# Ham-Dip-V2-003.net
KiCad netlist of a schematic drawn in EAGLE
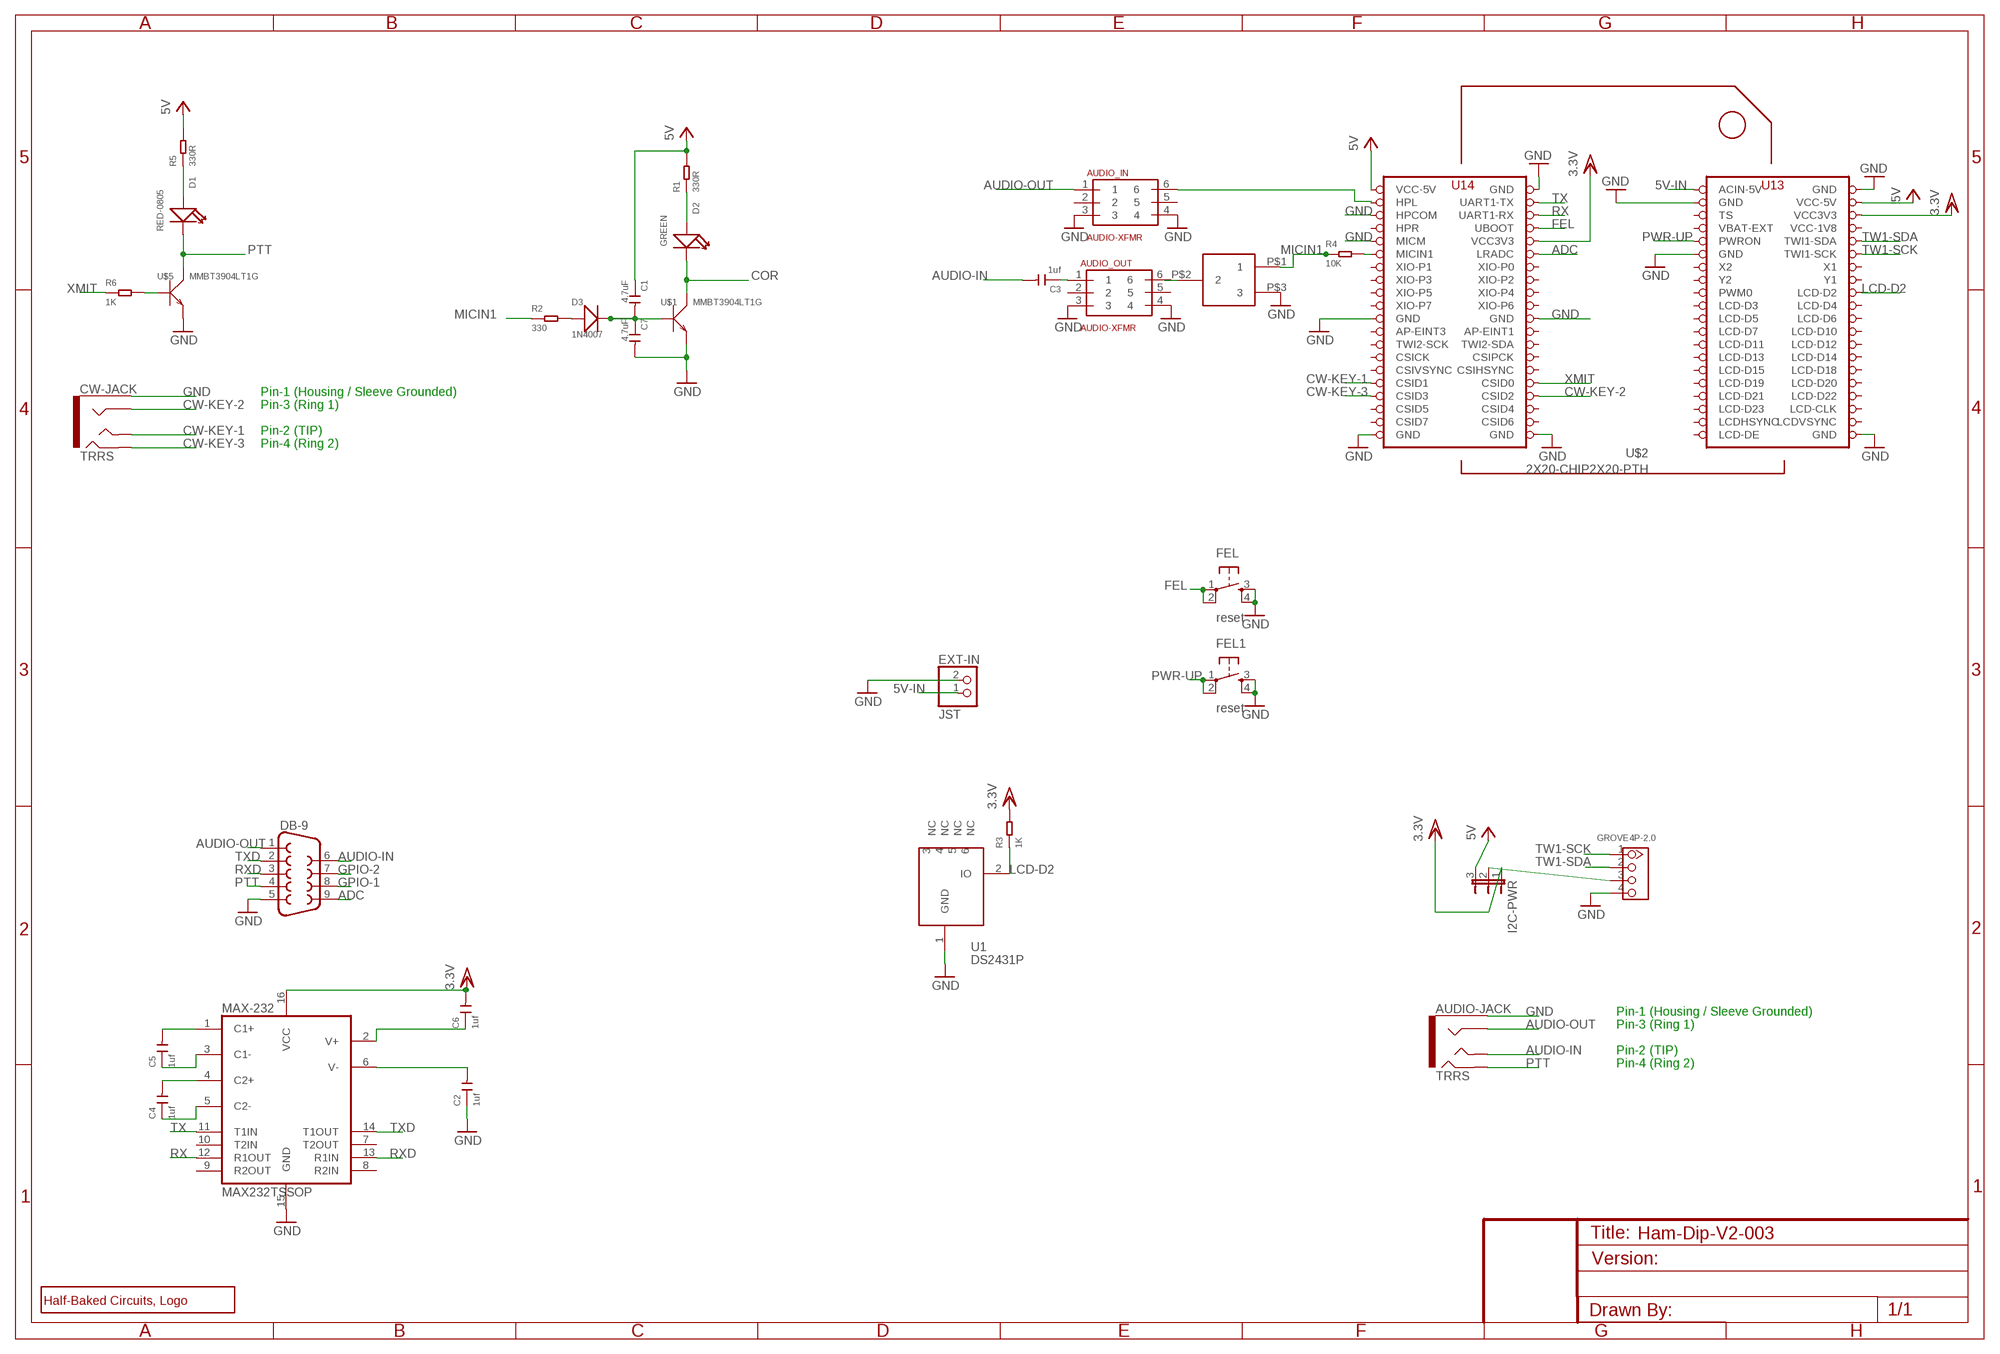
[diagram p0: schematic, sheet 1]

(export (version "E")
  (design (tool "Eeschema 10.0.6"))
  (components
    (comp (ref "AUDIO-JACK")
      (value "TRRS")
      (footprint "eagle-import:AUDIO-JACK-TRRS-SMD")
      (libsource (lib "eagle-import") (part "AUDIO-JACK3"))
    )
    (comp (ref "AUDIO_IN")
      (value "AUDIO-XFMR")
      (footprint "eagle-import:SM-LP-5001")
      (libsource (lib "eagle-import") (part "SM-LP-5001"))
    )
    (comp (ref "AUDIO_OUT")
      (value "AUDIO-XFMR")
      (footprint "eagle-import:SM-LP-5001")
      (libsource (lib "eagle-import") (part "SM-LP-5001"))
    )
    (comp (ref "C1")
      (value "4.7uF")
      (footprint "eagle-import:C0805")
      (fields (field (name "MPN") "CC0805KKX7R8BB105"))
      (libsource (lib "eagle-import") (part "CERAMIC-1UF-25V-10%-X7R(0805)"))
    )
    (comp (ref "C2")
      (value "1uf")
      (footprint "eagle-import:C0805")
      (fields (field (name "MPN") "CC0805KKX7R8BB105"))
      (libsource (lib "eagle-import") (part "CERAMIC-1UF-25V-10%-X7R(0805)"))
    )
    (comp (ref "C3")
      (value "1uf")
      (footprint "eagle-import:C0805")
      (fields (field (name "MPN") "CC0805KKX7R8BB105"))
      (libsource (lib "eagle-import") (part "CERAMIC-1UF-25V-10%-X7R(0805)"))
    )
    (comp (ref "C4")
      (value "1uf")
      (footprint "eagle-import:C0805")
      (fields (field (name "MPN") "CC0805KKX7R8BB105"))
      (libsource (lib "eagle-import") (part "CERAMIC-1UF-25V-10%-X7R(0805)"))
    )
    (comp (ref "C5")
      (value "1uf")
      (footprint "eagle-import:C0805")
      (fields (field (name "MPN") "CC0805KKX7R8BB105"))
      (libsource (lib "eagle-import") (part "CERAMIC-1UF-25V-10%-X7R(0805)"))
    )
    (comp (ref "C6")
      (value "1uf")
      (footprint "eagle-import:C0805")
      (fields (field (name "MPN") "CC0805KKX7R8BB105"))
      (libsource (lib "eagle-import") (part "CERAMIC-1UF-25V-10%-X7R(0805)"))
    )
    (comp (ref "C7")
      (value "4.7uF")
      (footprint "eagle-import:C0805")
      (fields (field (name "MPN") "CC0805KKX7R8BB105"))
      (libsource (lib "eagle-import") (part "CERAMIC-1UF-25V-10%-X7R(0805)"))
    )
    (comp (ref "CW-JACK")
      (value "TRRS")
      (footprint "eagle-import:AUDIO-JACK-TRRS-SMD")
      (libsource (lib "eagle-import") (part "AUDIO-JACK3"))
    )
    (comp (ref "D1")
      (value "RED-0805")
      (footprint "eagle-import:LED-0805")
      (fields (field (name "MPN") "17-215SURC/S530-A2/TR8"))
      (libsource (lib "eagle-import") (part "SMD-LED-CLEAR-RED(0805)"))
    )
    (comp (ref "D2")
      (value "GREEN")
      (footprint "eagle-import:LED-0805")
      (fields (field (name "MPN") "17-215SURC/S530-A2/TR8"))
      (libsource (lib "eagle-import") (part "SMD-LED-CLEAR-RED(0805)"))
    )
    (comp (ref "D3")
      (value "1N4007")
      (footprint "eagle-import:DO-214AC")
      (libsource (lib "eagle-import") (part "DIODE-GEN-PURPOSE-1KV-1A(DO-214AC)"))
    )
    (comp (ref "DB-9")
      (value "DB9FEMALE")
      (footprint "eagle-import:DB9")
      (libsource (lib "eagle-import") (part "DB9FEMALE"))
    )
    (comp (ref "EXT-IN")
      (value "JST")
      (footprint "eagle-import:JST-PH-2-THM")
      (libsource (lib "eagle-import") (part "JST_2PIN-THM"))
    )
    (comp (ref "FEL")
      (value "reset")
      (footprint "eagle-import:TACTILE_SWITCH_SMD")
      (libsource (lib "eagle-import") (part "TAC_SWITCHSMD"))
    )
    (comp (ref "FEL1")
      (value "reset")
      (footprint "eagle-import:TACTILE_SWITCH_SMD")
      (libsource (lib "eagle-import") (part "TAC_SWITCHSMD"))
    )
    (comp (ref "GROVE")
      (value "4P-2.0")
      (footprint "eagle-import:HW4-2.0")
      (libsource (lib "eagle-import") (part "GROVE-CONNECTOR-DIP(4P-2.0)"))
    )
    (comp (ref "I2C-PWR")
      (value "JP2E")
      (footprint "eagle-import:JP2")
      (libsource (lib "eagle-import") (part "JP2E"))
    )
    (comp (ref "MAX-232")
      (value "MAX232TSSOP")
      (footprint "eagle-import:TSSOP16")
      (libsource (lib "eagle-import") (part "MAX232TSSOP"))
    )
    (comp (ref "R1")
      (value "330R")
      (footprint "eagle-import:R0805")
      (fields (field (name "MPN") "RC0805JR-07220RL"))
      (libsource (lib "eagle-import") (part "SMD-RES-220R-5%-1/8W(0805)"))
    )
    (comp (ref "R2")
      (value "330")
      (footprint "eagle-import:R0805")
      (fields (field (name "MPN") "RC0805JR-07220RL"))
      (libsource (lib "eagle-import") (part "SMD-RES-220R-5%-1/8W(0805)"))
    )
    (comp (ref "R3")
      (value "1K")
      (footprint "eagle-import:R0805")
      (fields (field (name "MPN") "RC0805JR-07220RL"))
      (libsource (lib "eagle-import") (part "SMD-RES-220R-5%-1/8W(0805)"))
    )
    (comp (ref "R4")
      (value "10K")
      (footprint "eagle-import:R0805")
      (fields (field (name "MPN") "RC0805FR-0710KL"))
      (libsource (lib "eagle-import") (part "SMD-RES-10K-1%-1/8W(0805)"))
    )
    (comp (ref "R5")
      (value "330R")
      (footprint "eagle-import:R0805")
      (fields (field (name "MPN") "RC0805JR-07220RL"))
      (libsource (lib "eagle-import") (part "SMD-RES-220R-5%-1/8W(0805)"))
    )
    (comp (ref "R6")
      (value "1K")
      (footprint "eagle-import:R0805")
      (fields (field (name "MPN") "RC0805JR-07220RL"))
      (libsource (lib "eagle-import") (part "SMD-RES-220R-5%-1/8W(0805)"))
    )
    (comp (ref "U$1")
      (value "MMBT3904LT1G")
      (footprint "eagle-import:SOT-23")
      (libsource (lib "eagle-import") (part "SMD-TRANSISTORS-NPN-40V-200MA-MMBT3904LT1G(SOT-23)"))
    )
    (comp (ref "U$2")
      (value "2X20-CHIP2X20-PTH")
      (footprint "eagle-import:2X20CHIP-TH")
      (fields (field (name "VENDOR_PART_NUMBER") "AWHW40-G-SMD-R (single)"))
      (libsource (lib "eagle-import") (part "2X20-CHIP2X20-PTH-CHIP_A"))
    )
    (comp (ref "U$3")
      (value "TC33X")
      (footprint "eagle-import:TC33X")
      (libsource (lib "eagle-import") (part "TC33X"))
    )
    (comp (ref "U$4")
      (value "HAM-DIP")
      (footprint "eagle-import:HAM-DIP")
      (libsource (lib "eagle-import") (part "HAM-DIP"))
    )
    (comp (ref "U$5")
      (value "MMBT3904LT1G")
      (footprint "eagle-import:SOT-23")
      (libsource (lib "eagle-import") (part "SMD-TRANSISTORS-NPN-40V-200MA-MMBT3904LT1G(SOT-23)"))
    )
    (comp (ref "U1")
      (value "DS2431P")
      (footprint "eagle-import:TSOC6")
      (fields (field (name "MFG") "DIGIKEY") (field (name "VENDOR_PART_NUMBER") "DS2431P+T&R"))
      (libsource (lib "eagle-import") (part "DS2431P"))
    )
  )
  (nets
    (net (code "1") (name "/5V-IN") (class "Default")
      (node (ref "EXT-IN") (pin "1") (pinfunction "2_1") (pintype "passive"))
      (node (ref "U$2") (pin "CHG-IN") (pinfunction "ACIN-5V_CHG-IN") (pintype "passive"))
    )
    (net (code "2") (name "/ADC") (class "Default")
      (node (ref "DB-9") (pin "9") (pinfunction "9_9") (pintype "passive"))
      (node (ref "U$2") (pin "LRADC") (pinfunction "LRADC_LRADC") (pintype "passive"))
    )
    (net (code "3") (name "/AUDIO-IN") (class "Default")
      (node (ref "AUDIO-JACK") (pin "TIP") (pinfunction "TIP_TIP") (pintype "bidirectional"))
      (node (ref "C3") (pin "2") (pinfunction "2_2") (pintype "passive"))
      (node (ref "DB-9") (pin "6") (pinfunction "6_6") (pintype "passive"))
    )
    (net (code "4") (name "/AUDIO-OUT") (class "Default")
      (node (ref "AUDIO-JACK") (pin "RING1") (pinfunction "RING1_RING1") (pintype "bidirectional"))
      (node (ref "AUDIO_IN") (pin "1") (pinfunction "1_1") (pintype "bidirectional"))
      (node (ref "DB-9") (pin "1") (pinfunction "1_1") (pintype "passive"))
    )
    (net (code "5") (name "/COR") (class "Default")
      (node (ref "D2") (pin "-") (pinfunction "-_-") (pintype "passive"))
      (node (ref "U$1") (pin "3") (pinfunction "C_3") (pintype "passive"))
    )
    (net (code "6") (name "/CW-KEY-1") (class "Default")
      (node (ref "CW-JACK") (pin "TIP") (pinfunction "TIP_TIP") (pintype "bidirectional"))
      (node (ref "U$2") (pin "CSID1") (pinfunction "CSID1_CSID1") (pintype "passive"))
    )
    (net (code "7") (name "/CW-KEY-2") (class "Default")
      (node (ref "CW-JACK") (pin "RING1") (pinfunction "RING1_RING1") (pintype "bidirectional"))
      (node (ref "U$2") (pin "CSID2") (pinfunction "CSID2_CSID2") (pintype "passive"))
    )
    (net (code "8") (name "/CW-KEY-3") (class "Default")
      (node (ref "CW-JACK") (pin "RING2") (pinfunction "RING2_RING2") (pintype "bidirectional"))
      (node (ref "U$2") (pin "CSID3") (pinfunction "CSID3_CSID3") (pintype "passive"))
    )
    (net (code "9") (name "/FEL") (class "Default")
      (node (ref "FEL") (pin "1") (pinfunction "1_1") (pintype "passive"))
      (node (ref "FEL") (pin "2") (pinfunction "2_2") (pintype "passive"))
      (node (ref "U$2") (pin "FEL") (pinfunction "UBOOT_FEL") (pintype "passive"))
    )
    (net (code "10") (name "/GPIO-1") (class "Default")
      (node (ref "DB-9") (pin "8") (pinfunction "8_8") (pintype "passive"))
    )
    (net (code "11") (name "/GPIO-2") (class "Default")
      (node (ref "DB-9") (pin "7") (pinfunction "7_7") (pintype "passive"))
    )
    (net (code "12") (name "/LCD-D2") (class "Default")
      (node (ref "R3") (pin "1") (pinfunction "1_1") (pintype "passive"))
      (node (ref "U$2") (pin "LCD-D2") (pinfunction "LCD-D2_LCD-D2") (pintype "passive"))
      (node (ref "U1") (pin "2") (pinfunction "IO_2") (pintype "bidirectional"))
    )
    (net (code "13") (name "/MICIN1") (class "Default")
      (node (ref "R2") (pin "1") (pinfunction "1_1") (pintype "passive"))
      (node (ref "R4") (pin "2") (pinfunction "2_2") (pintype "passive"))
      (node (ref "U$2") (pin "MICIN1") (pinfunction "MICIN1_MICIN1") (pintype "passive"))
    )
    (net (code "14") (name "/PTT") (class "Default")
      (node (ref "AUDIO-JACK") (pin "RING2") (pinfunction "RING2_RING2") (pintype "bidirectional"))
      (node (ref "D1") (pin "-") (pinfunction "-_-") (pintype "passive"))
      (node (ref "DB-9") (pin "4") (pinfunction "4_4") (pintype "passive"))
      (node (ref "U$5") (pin "3") (pinfunction "C_3") (pintype "passive"))
    )
    (net (code "15") (name "/PWR-UP") (class "Default")
      (node (ref "FEL1") (pin "1") (pinfunction "1_1") (pintype "passive"))
      (node (ref "FEL1") (pin "2") (pinfunction "2_2") (pintype "passive"))
      (node (ref "U$2") (pin "PWRON") (pinfunction "PWRON_PWRON") (pintype "passive"))
    )
    (net (code "16") (name "/RX") (class "Default")
      (node (ref "MAX-232") (pin "12") (pinfunction "R1OUT_12") (pintype "output"))
      (node (ref "U$2") (pin "UART1-RX") (pinfunction "UART1-RX_UART1-RX") (pintype "passive"))
    )
    (net (code "17") (name "/RXD") (class "Default")
      (node (ref "DB-9") (pin "3") (pinfunction "3_3") (pintype "passive"))
      (node (ref "MAX-232") (pin "13") (pinfunction "R1IN_13") (pintype "input"))
    )
    (net (code "18") (name "/TW1-SCK") (class "Default")
      (node (ref "GROVE") (pin "1") (pinfunction "1_1") (pintype "bidirectional"))
      (node (ref "U$2") (pin "TWI1-SCK") (pinfunction "TWI1-SCK_TWI1-SCK") (pintype "passive"))
    )
    (net (code "19") (name "/TW1-SDA") (class "Default")
      (node (ref "GROVE") (pin "2") (pinfunction "2_2") (pintype "bidirectional"))
      (node (ref "U$2") (pin "TWI1-SDA") (pinfunction "TWI1-SDA_TWI1-SDA") (pintype "passive"))
    )
    (net (code "20") (name "/TX") (class "Default")
      (node (ref "MAX-232") (pin "11") (pinfunction "T1IN_11") (pintype "input"))
      (node (ref "U$2") (pin "UART1-TX") (pinfunction "UART1-TX_UART1-TX") (pintype "passive"))
    )
    (net (code "21") (name "/TXD") (class "Default")
      (node (ref "DB-9") (pin "2") (pinfunction "2_2") (pintype "passive"))
      (node (ref "MAX-232") (pin "14") (pinfunction "T1OUT_14") (pintype "output"))
    )
    (net (code "22") (name "/VCC-1V8") (class "Default")
      (node (ref "U$2") (pin "VCC1V8") (pinfunction "VCC-1V8_VCC1V8") (pintype "power_in"))
    )
    (net (code "23") (name "/XMIT") (class "Default")
      (node (ref "R6") (pin "1") (pinfunction "1_1") (pintype "passive"))
      (node (ref "U$2") (pin "CSID0") (pinfunction "CSID0_CSID0") (pintype "passive"))
    )
    (net (code "24") (name "3.3V") (class "Default")
      (node (ref "C6") (pin "2") (pinfunction "2_2") (pintype "passive"))
      (node (ref "I2C-PWR") (pin "1") (pinfunction "1_1") (pintype "passive"))
      (node (ref "MAX-232") (pin "16") (pinfunction "VCC_16") (pintype "bidirectional"))
      (node (ref "R3") (pin "2") (pinfunction "2_2") (pintype "passive"))
      (node (ref "U$2") (pin "VCC3V3") (pinfunction "VCC3V3_VCC3V3") (pintype "power_in"))
      (node (ref "U$2") (pin "VCC3V3@1") (pinfunction "VCC3V3_VCC3V3@1") (pintype "power_in"))
    )
    (net (code "25") (name "5V") (class "Default")
      (node (ref "C1") (pin "1") (pinfunction "1_1") (pintype "passive"))
      (node (ref "I2C-PWR") (pin "3") (pinfunction "3_3") (pintype "passive"))
      (node (ref "R1") (pin "2") (pinfunction "2_2") (pintype "passive"))
      (node (ref "R5") (pin "2") (pinfunction "2_2") (pintype "passive"))
      (node (ref "U$2") (pin "VCC5V@0") (pinfunction "VCC-5V_VCC5V@0") (pintype "power_in"))
      (node (ref "U$2") (pin "VCC5V@1") (pinfunction "VCC-5V_VCC5V@1") (pintype "power_in"))
    )
    (net (code "26") (name "GND") (class "Default")
      (node (ref "AUDIO-JACK") (pin "EARTH") (pinfunction "EARTH_EARTH") (pintype "bidirectional"))
      (node (ref "AUDIO_IN") (pin "3") (pinfunction "3_3") (pintype "bidirectional"))
      (node (ref "AUDIO_IN") (pin "4") (pinfunction "4_4") (pintype "bidirectional"))
      (node (ref "AUDIO_OUT") (pin "3") (pinfunction "3_3") (pintype "bidirectional"))
      (node (ref "AUDIO_OUT") (pin "4") (pinfunction "4_4") (pintype "bidirectional"))
      (node (ref "C2") (pin "1") (pinfunction "1_1") (pintype "passive"))
      (node (ref "C7") (pin "2") (pinfunction "2_2") (pintype "passive"))
      (node (ref "CW-JACK") (pin "EARTH") (pinfunction "EARTH_EARTH") (pintype "bidirectional"))
      (node (ref "DB-9") (pin "5") (pinfunction "5_5") (pintype "passive"))
      (node (ref "EXT-IN") (pin "2") (pinfunction "1_2") (pintype "passive"))
      (node (ref "FEL") (pin "3") (pinfunction "3_3") (pintype "passive"))
      (node (ref "FEL") (pin "4") (pinfunction "4_4") (pintype "passive"))
      (node (ref "FEL1") (pin "3") (pinfunction "3_3") (pintype "passive"))
      (node (ref "FEL1") (pin "4") (pinfunction "4_4") (pintype "passive"))
      (node (ref "GROVE") (pin "4") (pinfunction "4_4") (pintype "bidirectional"))
      (node (ref "MAX-232") (pin "15") (pinfunction "GND_15") (pintype "bidirectional"))
      (node (ref "U$1") (pin "2") (pinfunction "E_2") (pintype "passive"))
      (node (ref "U$2") (pin "GND@1") (pinfunction "GND_GND@1") (pintype "power_in"))
      (node (ref "U$2") (pin "GND@10") (pinfunction "GND_GND@10") (pintype "power_in"))
      (node (ref "U$2") (pin "GND@2") (pinfunction "GND_GND@2") (pintype "power_in"))
      (node (ref "U$2") (pin "GND@3") (pinfunction "GND_GND@3") (pintype "power_in"))
      (node (ref "U$2") (pin "GND@4") (pinfunction "GND_GND@4") (pintype "power_in"))
      (node (ref "U$2") (pin "GND@5") (pinfunction "GND_GND@5") (pintype "power_in"))
      (node (ref "U$2") (pin "GND@6") (pinfunction "GND_GND@6") (pintype "power_in"))
      (node (ref "U$2") (pin "GND@7") (pinfunction "GND_GND@7") (pintype "power_in"))
      (node (ref "U$2") (pin "GND@8") (pinfunction "GND_GND@8") (pintype "power_in"))
      (node (ref "U$2") (pin "HPCOM") (pinfunction "HPCOM_HPCOM") (pintype "passive"))
      (node (ref "U$2") (pin "MICM") (pinfunction "MICM_MICM") (pintype "passive"))
      (node (ref "U$3") (pin "P$3") (pinfunction "3_P$3") (pintype "bidirectional"))
      (node (ref "U$5") (pin "2") (pinfunction "E_2") (pintype "passive"))
      (node (ref "U1") (pin "1") (pinfunction "GND_1") (pintype "bidirectional"))
    )
    (net (code "27") (name "Net-(AUDIO_IN-Pad6)") (class "Default")
      (node (ref "AUDIO_IN") (pin "6") (pinfunction "6_6") (pintype "bidirectional"))
      (node (ref "U$2") (pin "HPL") (pinfunction "HPL_HPL") (pintype "passive"))
    )
    (net (code "28") (name "Net-(AUDIO_OUT-Pad1)") (class "Default")
      (node (ref "AUDIO_OUT") (pin "1") (pinfunction "1_1") (pintype "bidirectional"))
      (node (ref "C3") (pin "1") (pinfunction "1_1") (pintype "passive"))
    )
    (net (code "29") (name "Net-(D1-Pad+)") (class "Default")
      (node (ref "D1") (pin "+") (pinfunction "+_+") (pintype "passive"))
      (node (ref "R5") (pin "1") (pinfunction "1_1") (pintype "passive"))
    )
    (net (code "30") (name "Net-(D2-Pad+)") (class "Default")
      (node (ref "D2") (pin "+") (pinfunction "+_+") (pintype "passive"))
      (node (ref "R1") (pin "1") (pinfunction "1_1") (pintype "passive"))
    )
    (net (code "31") (name "Net-(D3-+)") (class "Default")
      (node (ref "D3") (pin "1") (pinfunction "+_1") (pintype "passive"))
      (node (ref "R2") (pin "2") (pinfunction "2_2") (pintype "passive"))
    )
    (net (code "32") (name "Net-(D3--)") (class "Default")
      (node (ref "C1") (pin "2") (pinfunction "2_2") (pintype "passive"))
      (node (ref "C7") (pin "1") (pinfunction "1_1") (pintype "passive"))
      (node (ref "D3") (pin "2") (pinfunction "-_2") (pintype "passive"))
      (node (ref "U$1") (pin "1") (pinfunction "B_1") (pintype "passive"))
    )
    (net (code "33") (name "Net-(GROVE-Pad3)") (class "Default")
      (node (ref "GROVE") (pin "3") (pinfunction "3_3") (pintype "bidirectional"))
      (node (ref "I2C-PWR") (pin "2") (pinfunction "2_2") (pintype "passive"))
    )
    (net (code "34") (name "Net-(MAX-232-C1+)") (class "Default")
      (node (ref "C5") (pin "2") (pinfunction "2_2") (pintype "passive"))
      (node (ref "MAX-232") (pin "1") (pinfunction "C1+_1") (pintype "bidirectional"))
    )
    (net (code "35") (name "Net-(MAX-232-C1-)") (class "Default")
      (node (ref "C5") (pin "1") (pinfunction "1_1") (pintype "passive"))
      (node (ref "MAX-232") (pin "3") (pinfunction "C1-_3") (pintype "bidirectional"))
    )
    (net (code "36") (name "Net-(MAX-232-C2+)") (class "Default")
      (node (ref "C4") (pin "2") (pinfunction "2_2") (pintype "passive"))
      (node (ref "MAX-232") (pin "4") (pinfunction "C2+_4") (pintype "bidirectional"))
    )
    (net (code "37") (name "Net-(MAX-232-C2-)") (class "Default")
      (node (ref "C4") (pin "1") (pinfunction "1_1") (pintype "passive"))
      (node (ref "MAX-232") (pin "5") (pinfunction "C2-_5") (pintype "bidirectional"))
    )
    (net (code "38") (name "Net-(MAX-232-V+)") (class "Default")
      (node (ref "C6") (pin "1") (pinfunction "1_1") (pintype "passive"))
      (node (ref "MAX-232") (pin "2") (pinfunction "V+_2") (pintype "bidirectional"))
    )
    (net (code "39") (name "Net-(MAX-232-V-)") (class "Default")
      (node (ref "C2") (pin "2") (pinfunction "2_2") (pintype "passive"))
      (node (ref "MAX-232") (pin "6") (pinfunction "V-_6") (pintype "bidirectional"))
    )
    (net (code "40") (name "Net-(U$3-1)") (class "Default")
      (node (ref "R4") (pin "1") (pinfunction "1_1") (pintype "passive"))
      (node (ref "U$3") (pin "P$1") (pinfunction "1_P$1") (pintype "bidirectional"))
    )
    (net (code "41") (name "Net-(U$5-B)") (class "Default")
      (node (ref "R6") (pin "2") (pinfunction "2_2") (pintype "passive"))
      (node (ref "U$5") (pin "1") (pinfunction "B_1") (pintype "passive"))
    )
    (net (code "42") (name "unconnected-(AUDIO_IN-Pad2)") (class "Default")
      (node (ref "AUDIO_IN") (pin "2") (pinfunction "2_2") (pintype "bidirectional"))
    )
    (net (code "43") (name "unconnected-(AUDIO_IN-Pad5)") (class "Default")
      (node (ref "AUDIO_IN") (pin "5") (pinfunction "5_5") (pintype "bidirectional"))
    )
    (net (code "44") (name "unconnected-(AUDIO_OUT-Pad2)") (class "Default")
      (node (ref "AUDIO_OUT") (pin "2") (pinfunction "2_2") (pintype "bidirectional"))
    )
    (net (code "45") (name "unconnected-(AUDIO_OUT-Pad5)") (class "Default")
      (node (ref "AUDIO_OUT") (pin "5") (pinfunction "5_5") (pintype "bidirectional"))
    )
    (net (code "46") (name "unconnected-(AUDIO_OUT-Pad6)") (class "Default")
      (node (ref "AUDIO_OUT") (pin "6") (pinfunction "6_6") (pintype "bidirectional"))
    )
    (net (code "47") (name "unconnected-(MAX-232-R2IN-Pad8)") (class "Default")
      (node (ref "MAX-232") (pin "8") (pinfunction "R2IN_8") (pintype "input"))
    )
    (net (code "48") (name "unconnected-(MAX-232-R2OUT-Pad9)") (class "Default")
      (node (ref "MAX-232") (pin "9") (pinfunction "R2OUT_9") (pintype "output"))
    )
    (net (code "49") (name "unconnected-(MAX-232-T2IN-Pad10)") (class "Default")
      (node (ref "MAX-232") (pin "10") (pinfunction "T2IN_10") (pintype "input"))
    )
    (net (code "50") (name "unconnected-(MAX-232-T2OUT-Pad7)") (class "Default")
      (node (ref "MAX-232") (pin "7") (pinfunction "T2OUT_7") (pintype "output"))
    )
    (net (code "51") (name "unconnected-(U$2-LCDHSYNC-PadLCD-HSYNC)") (class "Default")
      (node (ref "U$2") (pin "LCD-HSYNC") (pinfunction "LCDHSYNC_LCD-HSYNC") (pintype "passive"))
    )
    (net (code "52") (name "unconnected-(U$2-LCDVSYNC-PadLCD-VSYNC)") (class "Default")
      (node (ref "U$2") (pin "LCD-VSYNC") (pinfunction "LCDVSYNC_LCD-VSYNC") (pintype "passive"))
    )
    (net (code "53") (name "unconnected-(U$2-PadAP-EINT1)") (class "Default")
      (node (ref "U$2") (pin "AP-EINT1") (pinfunction "AP-EINT1_AP-EINT1") (pintype "passive"))
    )
    (net (code "54") (name "unconnected-(U$2-PadAP-EINT3)") (class "Default")
      (node (ref "U$2") (pin "AP-EINT3") (pinfunction "AP-EINT3_AP-EINT3") (pintype "passive"))
    )
    (net (code "55") (name "unconnected-(U$2-PadCSICK)") (class "Default")
      (node (ref "U$2") (pin "CSICK") (pinfunction "CSICK_CSICK") (pintype "passive"))
    )
    (net (code "56") (name "unconnected-(U$2-PadCSID4)") (class "Default")
      (node (ref "U$2") (pin "CSID4") (pinfunction "CSID4_CSID4") (pintype "passive"))
    )
    (net (code "57") (name "unconnected-(U$2-PadCSID5)") (class "Default")
      (node (ref "U$2") (pin "CSID5") (pinfunction "CSID5_CSID5") (pintype "passive"))
    )
    (net (code "58") (name "unconnected-(U$2-PadCSID6)") (class "Default")
      (node (ref "U$2") (pin "CSID6") (pinfunction "CSID6_CSID6") (pintype "passive"))
    )
    (net (code "59") (name "unconnected-(U$2-PadCSID7)") (class "Default")
      (node (ref "U$2") (pin "CSID7") (pinfunction "CSID7_CSID7") (pintype "passive"))
    )
    (net (code "60") (name "unconnected-(U$2-PadCSIHSYNC)") (class "Default")
      (node (ref "U$2") (pin "CSIHSYNC") (pinfunction "CSIHSYNC_CSIHSYNC") (pintype "passive"))
    )
    (net (code "61") (name "unconnected-(U$2-PadCSIPCK)") (class "Default")
      (node (ref "U$2") (pin "CSIPCK") (pinfunction "CSIPCK_CSIPCK") (pintype "passive"))
    )
    (net (code "62") (name "unconnected-(U$2-PadCSIVSYNC)") (class "Default")
      (node (ref "U$2") (pin "CSIVSYNC") (pinfunction "CSIVSYNC_CSIVSYNC") (pintype "passive"))
    )
    (net (code "63") (name "unconnected-(U$2-PadHPR)") (class "Default")
      (node (ref "U$2") (pin "HPR") (pinfunction "HPR_HPR") (pintype "passive"))
    )
    (net (code "64") (name "unconnected-(U$2-PadLCD-CLK)") (class "Default")
      (node (ref "U$2") (pin "LCD-CLK") (pinfunction "LCD-CLK_LCD-CLK") (pintype "passive"))
    )
    (net (code "65") (name "unconnected-(U$2-PadLCD-D3)") (class "Default")
      (node (ref "U$2") (pin "LCD-D3") (pinfunction "LCD-D3_LCD-D3") (pintype "passive"))
    )
    (net (code "66") (name "unconnected-(U$2-PadLCD-D4)") (class "Default")
      (node (ref "U$2") (pin "LCD-D4") (pinfunction "LCD-D4_LCD-D4") (pintype "passive"))
    )
    (net (code "67") (name "unconnected-(U$2-PadLCD-D5)") (class "Default")
      (node (ref "U$2") (pin "LCD-D5") (pinfunction "LCD-D5_LCD-D5") (pintype "passive"))
    )
    (net (code "68") (name "unconnected-(U$2-PadLCD-D6)") (class "Default")
      (node (ref "U$2") (pin "LCD-D6") (pinfunction "LCD-D6_LCD-D6") (pintype "passive"))
    )
    (net (code "69") (name "unconnected-(U$2-PadLCD-D7)") (class "Default")
      (node (ref "U$2") (pin "LCD-D7") (pinfunction "LCD-D7_LCD-D7") (pintype "passive"))
    )
    (net (code "70") (name "unconnected-(U$2-PadLCD-D10)") (class "Default")
      (node (ref "U$2") (pin "LCD-D10") (pinfunction "LCD-D10_LCD-D10") (pintype "passive"))
    )
    (net (code "71") (name "unconnected-(U$2-PadLCD-D11)") (class "Default")
      (node (ref "U$2") (pin "LCD-D11") (pinfunction "LCD-D11_LCD-D11") (pintype "passive"))
    )
    (net (code "72") (name "unconnected-(U$2-PadLCD-D12)") (class "Default")
      (node (ref "U$2") (pin "LCD-D12") (pinfunction "LCD-D12_LCD-D12") (pintype "passive"))
    )
    (net (code "73") (name "unconnected-(U$2-PadLCD-D13)") (class "Default")
      (node (ref "U$2") (pin "LCD-D13") (pinfunction "LCD-D13_LCD-D13") (pintype "passive"))
    )
    (net (code "74") (name "unconnected-(U$2-PadLCD-D14)") (class "Default")
      (node (ref "U$2") (pin "LCD-D14") (pinfunction "LCD-D14_LCD-D14") (pintype "passive"))
    )
    (net (code "75") (name "unconnected-(U$2-PadLCD-D15)") (class "Default")
      (node (ref "U$2") (pin "LCD-D15") (pinfunction "LCD-D15_LCD-D15") (pintype "passive"))
    )
    (net (code "76") (name "unconnected-(U$2-PadLCD-D18)") (class "Default")
      (node (ref "U$2") (pin "LCD-D18") (pinfunction "LCD-D18_LCD-D18") (pintype "passive"))
    )
    (net (code "77") (name "unconnected-(U$2-PadLCD-D19)") (class "Default")
      (node (ref "U$2") (pin "LCD-D19") (pinfunction "LCD-D19_LCD-D19") (pintype "passive"))
    )
    (net (code "78") (name "unconnected-(U$2-PadLCD-D20)") (class "Default")
      (node (ref "U$2") (pin "LCD-D20") (pinfunction "LCD-D20_LCD-D20") (pintype "passive"))
    )
    (net (code "79") (name "unconnected-(U$2-PadLCD-D21)") (class "Default")
      (node (ref "U$2") (pin "LCD-D21") (pinfunction "LCD-D21_LCD-D21") (pintype "passive"))
    )
    (net (code "80") (name "unconnected-(U$2-PadLCD-D22)") (class "Default")
      (node (ref "U$2") (pin "LCD-D22") (pinfunction "LCD-D22_LCD-D22") (pintype "passive"))
    )
    (net (code "81") (name "unconnected-(U$2-PadLCD-D23)") (class "Default")
      (node (ref "U$2") (pin "LCD-D23") (pinfunction "LCD-D23_LCD-D23") (pintype "passive"))
    )
    (net (code "82") (name "unconnected-(U$2-PadLCD-DE)") (class "Default")
      (node (ref "U$2") (pin "LCD-DE") (pinfunction "LCD-DE_LCD-DE") (pintype "passive"))
    )
    (net (code "83") (name "unconnected-(U$2-PadPWM0)") (class "Default")
      (node (ref "U$2") (pin "PWM0") (pinfunction "PWM0_PWM0") (pintype "passive"))
    )
    (net (code "84") (name "unconnected-(U$2-PadTS)") (class "Default")
      (node (ref "U$2") (pin "TS") (pinfunction "TS_TS") (pintype "passive"))
    )
    (net (code "85") (name "unconnected-(U$2-PadTWI2-SCK)") (class "Default")
      (node (ref "U$2") (pin "TWI2-SCK") (pinfunction "TWI2-SCK_TWI2-SCK") (pintype "passive"))
    )
    (net (code "86") (name "unconnected-(U$2-PadTWI2-SDA)") (class "Default")
      (node (ref "U$2") (pin "TWI2-SDA") (pinfunction "TWI2-SDA_TWI2-SDA") (pintype "passive"))
    )
    (net (code "87") (name "unconnected-(U$2-PadX1)") (class "Default")
      (node (ref "U$2") (pin "X1") (pinfunction "X1_X1") (pintype "passive"))
    )
    (net (code "88") (name "unconnected-(U$2-PadX2)") (class "Default")
      (node (ref "U$2") (pin "X2") (pinfunction "X2_X2") (pintype "passive"))
    )
    (net (code "89") (name "unconnected-(U$2-PadXIO-P0)") (class "Default")
      (node (ref "U$2") (pin "XIO-P0") (pinfunction "XIO-P0_XIO-P0") (pintype "passive"))
    )
    (net (code "90") (name "unconnected-(U$2-PadXIO-P1)") (class "Default")
      (node (ref "U$2") (pin "XIO-P1") (pinfunction "XIO-P1_XIO-P1") (pintype "passive"))
    )
    (net (code "91") (name "unconnected-(U$2-PadXIO-P2)") (class "Default")
      (node (ref "U$2") (pin "XIO-P2") (pinfunction "XIO-P2_XIO-P2") (pintype "passive"))
    )
    (net (code "92") (name "unconnected-(U$2-PadXIO-P3)") (class "Default")
      (node (ref "U$2") (pin "XIO-P3") (pinfunction "XIO-P3_XIO-P3") (pintype "passive"))
    )
    (net (code "93") (name "unconnected-(U$2-PadXIO-P4)") (class "Default")
      (node (ref "U$2") (pin "XIO-P4") (pinfunction "XIO-P4_XIO-P4") (pintype "passive"))
    )
    (net (code "94") (name "unconnected-(U$2-PadXIO-P5)") (class "Default")
      (node (ref "U$2") (pin "XIO-P5") (pinfunction "XIO-P5_XIO-P5") (pintype "passive"))
    )
    (net (code "95") (name "unconnected-(U$2-PadXIO-P6)") (class "Default")
      (node (ref "U$2") (pin "XIO-P6") (pinfunction "XIO-P6_XIO-P6") (pintype "passive"))
    )
    (net (code "96") (name "unconnected-(U$2-PadXIO-P7)") (class "Default")
      (node (ref "U$2") (pin "XIO-P7") (pinfunction "XIO-P7_XIO-P7") (pintype "passive"))
    )
    (net (code "97") (name "unconnected-(U$2-PadY1)") (class "Default")
      (node (ref "U$2") (pin "Y1") (pinfunction "Y1_Y1") (pintype "passive"))
    )
    (net (code "98") (name "unconnected-(U$2-PadY2)") (class "Default")
      (node (ref "U$2") (pin "Y2") (pinfunction "Y2_Y2") (pintype "passive"))
    )
    (net (code "99") (name "unconnected-(U$2-VBAT-EXT-PadBAT)") (class "Default")
      (node (ref "U$2") (pin "BAT") (pinfunction "VBAT-EXT_BAT") (pintype "passive"))
    )
    (net (code "100") (name "unconnected-(U$3-2-PadP$2)") (class "Default")
      (node (ref "U$3") (pin "P$2") (pinfunction "2_P$2") (pintype "bidirectional"))
    )
    (net (code "101") (name "unconnected-(U1-NC-Pad3)") (class "Default")
      (node (ref "U1") (pin "3") (pinfunction "NC_3") (pintype "bidirectional"))
    )
    (net (code "102") (name "unconnected-(U1-NC-Pad4)") (class "Default")
      (node (ref "U1") (pin "4") (pinfunction "NC_4") (pintype "bidirectional"))
    )
    (net (code "103") (name "unconnected-(U1-NC-Pad5)") (class "Default")
      (node (ref "U1") (pin "5") (pinfunction "NC_5") (pintype "bidirectional"))
    )
    (net (code "104") (name "unconnected-(U1-NC-Pad6)") (class "Default")
      (node (ref "U1") (pin "6") (pinfunction "NC_6") (pintype "bidirectional"))
    )
  )
)
